# 22_USB3_0_device.net
KiCad netlist of a schematic drawn in Altium Designer
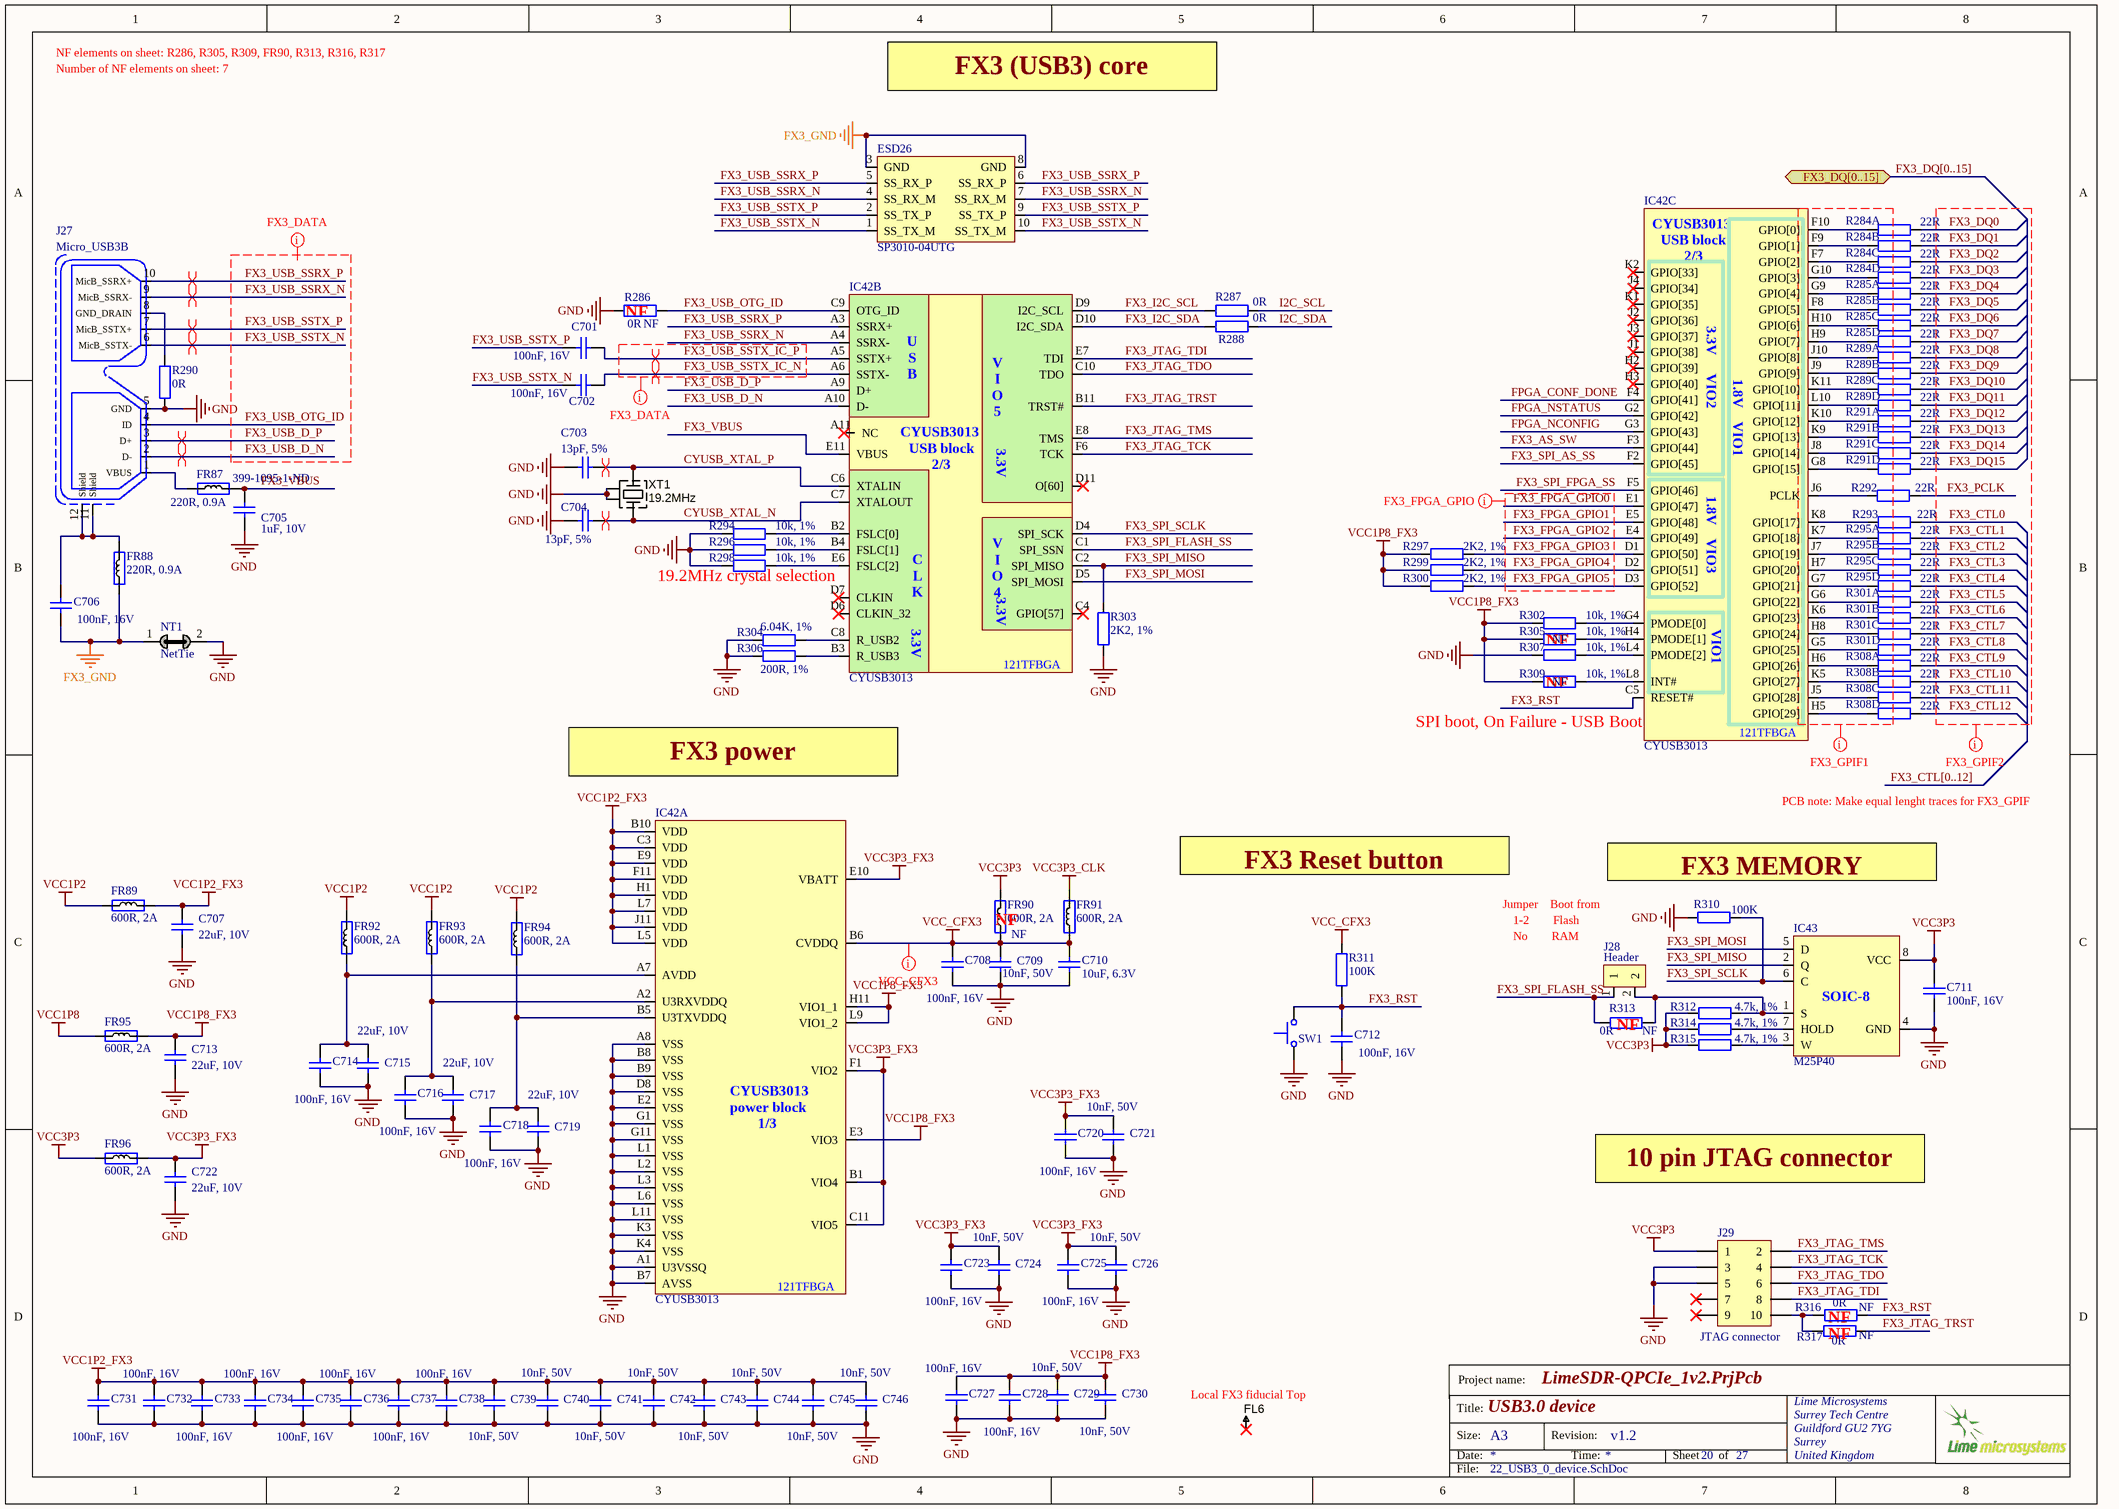
[diagram p0: 22_USB3_0_device.SchDoc]

(export (version "E")
  (design (tool "Eeschema 10.0.6"))
  (components
    (comp (ref "C701")
      (value "100nF, 16V")
      (footprint "CAP0402")
      (fields
        (field (name "TOLERANCE") "10 %")
        (field (name "MANUFACTURER") "Murata Electronics")
        (field (name "MANUFACTURER PART NUMBER") "GRM155R71C104KA88D")
      )
      (libsource (lib "LimeFPGAboard_schLib") (part "Cap_0603"))
    )
    (comp (ref "C702")
      (value "100nF, 16V")
      (footprint "CAP0402")
      (fields
        (field (name "TOLERANCE") "10 %")
        (field (name "MANUFACTURER") "Murata Electronics")
        (field (name "MANUFACTURER PART NUMBER") "GRM155R71C104KA88D")
      )
      (libsource (lib "LimeFPGAboard_schLib") (part "Cap_0603"))
    )
    (comp (ref "C703")
      (value "13pF, 5%")
      (footprint "CAP0402")
      (fields
        (field (name "TOLERANCE") "±5%")
        (field (name "MANUFACTURER") "Murata Electronics North America")
      )
      (libsource (lib "LimeFPGAboard_schLib") (part "Cap_0603"))
    )
    (comp (ref "C704")
      (value "13pF, 5%")
      (footprint "CAP0402")
      (fields
        (field (name "TOLERANCE") "±5%")
        (field (name "MANUFACTURER") "Murata Electronics North America")
      )
      (libsource (lib "LimeFPGAboard_schLib") (part "Cap_0603"))
    )
    (comp (ref "C705")
      (value "1uF, 10V")
      (footprint "CAP0603")
      (fields
        (field (name "SUPPLIER PART NUMBER 1") "399-1095-1-ND")
        (field (name "MANUFACTURER") "KEMET")
        (field (name "TOLERANCE") "±10%")
      )
      (libsource (lib "LimeFPGAboard_schLib") (part "Cap_0603"))
    )
    (comp (ref "C706")
      (value "100nF, 16V")
      (footprint "CAP0402")
      (fields
        (field (name "TOLERANCE") "10 %")
        (field (name "MANUFACTURER") "Murata Electronics")
        (field (name "MANUFACTURER PART NUMBER") "GRM155R71C104KA88D")
      )
      (libsource (lib "LimeFPGAboard_schLib") (part "Cap_0603"))
    )
    (comp (ref "C707")
      (value "22uF, 10V")
      (footprint "CAP0603")
      (fields (field (name "TOLERANCE") "20 %") (field (name "MANUFACTURER") "TDK Corporation"))
      (libsource (lib "LimeFPGAboard_schLib") (part "Cap_0603"))
    )
    (comp (ref "C708")
      (value "100nF, 16V")
      (footprint "CAP0402")
      (fields
        (field (name "TOLERANCE") "10 %")
        (field (name "MANUFACTURER") "Murata Electronics")
        (field (name "MANUFACTURER PART NUMBER") "GRM155R71C104KA88D")
      )
      (libsource (lib "LimeFPGAboard_schLib") (part "Cap_0603"))
    )
    (comp (ref "C709")
      (value "10nF, 50V")
      (footprint "CAP0402")
      (fields (field (name "TOLERANCE") "±10%") (field (name "MANUFACTURER") "Yageo"))
      (libsource (lib "LimeFPGAboard_schLib") (part "Cap_0603"))
    )
    (comp (ref "C710")
      (value "10uF, 6.3V")
      (footprint "CAP0603")
      (fields (field (name "TOLERANCE") "±20%") (field (name "MANUFACTURER") "Yageo"))
      (libsource (lib "LimeFPGAboard_schLib") (part "Cap_0603"))
    )
    (comp (ref "C711")
      (value "100nF, 16V")
      (footprint "CAP0402")
      (fields
        (field (name "TOLERANCE") "10 %")
        (field (name "MANUFACTURER") "Murata Electronics")
        (field (name "MANUFACTURER PART NUMBER") "GRM155R71C104KA88D")
      )
      (libsource (lib "LimeFPGAboard_schLib") (part "Cap_0603"))
    )
    (comp (ref "C712")
      (value "100nF, 16V")
      (footprint "CAP0402")
      (fields
        (field (name "TOLERANCE") "10 %")
        (field (name "MANUFACTURER") "Murata Electronics")
        (field (name "MANUFACTURER PART NUMBER") "GRM155R71C104KA88D")
      )
      (libsource (lib "LimeFPGAboard_schLib") (part "Cap_0603"))
    )
    (comp (ref "C713")
      (value "22uF, 10V")
      (footprint "CAP0603")
      (fields (field (name "TOLERANCE") "20 %") (field (name "MANUFACTURER") "TDK Corporation"))
      (libsource (lib "LimeFPGAboard_schLib") (part "Cap_0603"))
    )
    (comp (ref "C714")
      (value "100nF, 16V")
      (footprint "CAP0402")
      (fields
        (field (name "TOLERANCE") "10 %")
        (field (name "MANUFACTURER") "Murata Electronics")
        (field (name "MANUFACTURER PART NUMBER") "GRM155R71C104KA88D")
      )
      (libsource (lib "LimeFPGAboard_schLib") (part "Cap_0603"))
    )
    (comp (ref "C715")
      (value "22uF, 10V")
      (footprint "CAP0603")
      (fields (field (name "TOLERANCE") "20 %") (field (name "MANUFACTURER") "TDK Corporation"))
      (libsource (lib "LimeFPGAboard_schLib") (part "Cap_0603"))
    )
    (comp (ref "C716")
      (value "100nF, 16V")
      (footprint "CAP0402")
      (fields
        (field (name "TOLERANCE") "10 %")
        (field (name "MANUFACTURER") "Murata Electronics")
        (field (name "MANUFACTURER PART NUMBER") "GRM155R71C104KA88D")
      )
      (libsource (lib "LimeFPGAboard_schLib") (part "Cap_0603"))
    )
    (comp (ref "C717")
      (value "22uF, 10V")
      (footprint "CAP0603")
      (fields (field (name "TOLERANCE") "20 %") (field (name "MANUFACTURER") "TDK Corporation"))
      (libsource (lib "LimeFPGAboard_schLib") (part "Cap_0603"))
    )
    (comp (ref "C718")
      (value "100nF, 16V")
      (footprint "CAP0402")
      (fields
        (field (name "TOLERANCE") "10 %")
        (field (name "MANUFACTURER") "Murata Electronics")
        (field (name "MANUFACTURER PART NUMBER") "GRM155R71C104KA88D")
      )
      (libsource (lib "LimeFPGAboard_schLib") (part "Cap_0603"))
    )
    (comp (ref "C719")
      (value "22uF, 10V")
      (footprint "CAP0603")
      (fields (field (name "TOLERANCE") "20 %") (field (name "MANUFACTURER") "TDK Corporation"))
      (libsource (lib "LimeFPGAboard_schLib") (part "Cap_0603"))
    )
    (comp (ref "C720")
      (value "100nF, 16V")
      (footprint "CAP0402")
      (fields
        (field (name "TOLERANCE") "10 %")
        (field (name "MANUFACTURER") "Murata Electronics")
        (field (name "MANUFACTURER PART NUMBER") "GRM155R71C104KA88D")
      )
      (libsource (lib "LimeFPGAboard_schLib") (part "Cap_0603"))
    )
    (comp (ref "C721")
      (value "10nF, 50V")
      (footprint "CAP0402")
      (fields (field (name "TOLERANCE") "±10%") (field (name "MANUFACTURER") "Yageo"))
      (libsource (lib "LimeFPGAboard_schLib") (part "Cap_0603"))
    )
    (comp (ref "C722")
      (value "22uF, 10V")
      (footprint "CAP0603")
      (fields (field (name "TOLERANCE") "20 %") (field (name "MANUFACTURER") "TDK Corporation"))
      (libsource (lib "LimeFPGAboard_schLib") (part "Cap_0603"))
    )
    (comp (ref "C723")
      (value "100nF, 16V")
      (footprint "CAP0402")
      (fields
        (field (name "TOLERANCE") "10 %")
        (field (name "MANUFACTURER") "Murata Electronics")
        (field (name "MANUFACTURER PART NUMBER") "GRM155R71C104KA88D")
      )
      (libsource (lib "LimeFPGAboard_schLib") (part "Cap_0603"))
    )
    (comp (ref "C724")
      (value "10nF, 50V")
      (footprint "CAP0402")
      (fields (field (name "TOLERANCE") "±10%") (field (name "MANUFACTURER") "Yageo"))
      (libsource (lib "LimeFPGAboard_schLib") (part "Cap_0603"))
    )
    (comp (ref "C725")
      (value "100nF, 16V")
      (footprint "CAP0402")
      (fields
        (field (name "TOLERANCE") "10 %")
        (field (name "MANUFACTURER") "Murata Electronics")
        (field (name "MANUFACTURER PART NUMBER") "GRM155R71C104KA88D")
      )
      (libsource (lib "LimeFPGAboard_schLib") (part "Cap_0603"))
    )
    (comp (ref "C726")
      (value "10nF, 50V")
      (footprint "CAP0402")
      (fields (field (name "TOLERANCE") "±10%") (field (name "MANUFACTURER") "Yageo"))
      (libsource (lib "LimeFPGAboard_schLib") (part "Cap_0603"))
    )
    (comp (ref "C727")
      (value "100nF, 16V")
      (footprint "CAP0402")
      (fields
        (field (name "TOLERANCE") "10 %")
        (field (name "MANUFACTURER") "Murata Electronics")
        (field (name "MANUFACTURER PART NUMBER") "GRM155R71C104KA88D")
      )
      (libsource (lib "LimeFPGAboard_schLib") (part "Cap_0603"))
    )
    (comp (ref "C728")
      (value "100nF, 16V")
      (footprint "CAP0402")
      (fields
        (field (name "TOLERANCE") "10 %")
        (field (name "MANUFACTURER") "Murata Electronics")
        (field (name "MANUFACTURER PART NUMBER") "GRM155R71C104KA88D")
      )
      (libsource (lib "LimeFPGAboard_schLib") (part "Cap_0603"))
    )
    (comp (ref "C729")
      (value "10nF, 50V")
      (footprint "CAP0402")
      (fields (field (name "TOLERANCE") "±10%") (field (name "MANUFACTURER") "Yageo"))
      (libsource (lib "LimeFPGAboard_schLib") (part "Cap_0603"))
    )
    (comp (ref "C730")
      (value "10nF, 50V")
      (footprint "CAP0402")
      (fields (field (name "TOLERANCE") "±10%") (field (name "MANUFACTURER") "Yageo"))
      (libsource (lib "LimeFPGAboard_schLib") (part "Cap_0603"))
    )
    (comp (ref "C731")
      (value "100nF, 16V")
      (footprint "CAP0402")
      (fields
        (field (name "TOLERANCE") "10 %")
        (field (name "MANUFACTURER") "Murata Electronics")
        (field (name "MANUFACTURER PART NUMBER") "GRM155R71C104KA88D")
      )
      (libsource (lib "LimeFPGAboard_schLib") (part "Cap_0603"))
    )
    (comp (ref "C732")
      (value "100nF, 16V")
      (footprint "CAP0402")
      (fields
        (field (name "TOLERANCE") "10 %")
        (field (name "MANUFACTURER") "Murata Electronics")
        (field (name "MANUFACTURER PART NUMBER") "GRM155R71C104KA88D")
      )
      (libsource (lib "LimeFPGAboard_schLib") (part "Cap_0603"))
    )
    (comp (ref "C733")
      (value "100nF, 16V")
      (footprint "CAP0402")
      (fields
        (field (name "TOLERANCE") "10 %")
        (field (name "MANUFACTURER") "Murata Electronics")
        (field (name "MANUFACTURER PART NUMBER") "GRM155R71C104KA88D")
      )
      (libsource (lib "LimeFPGAboard_schLib") (part "Cap_0603"))
    )
    (comp (ref "C734")
      (value "100nF, 16V")
      (footprint "CAP0402")
      (fields
        (field (name "TOLERANCE") "10 %")
        (field (name "MANUFACTURER") "Murata Electronics")
        (field (name "MANUFACTURER PART NUMBER") "GRM155R71C104KA88D")
      )
      (libsource (lib "LimeFPGAboard_schLib") (part "Cap_0603"))
    )
    (comp (ref "C735")
      (value "100nF, 16V")
      (footprint "CAP0402")
      (fields
        (field (name "TOLERANCE") "10 %")
        (field (name "MANUFACTURER") "Murata Electronics")
        (field (name "MANUFACTURER PART NUMBER") "GRM155R71C104KA88D")
      )
      (libsource (lib "LimeFPGAboard_schLib") (part "Cap_0603"))
    )
    (comp (ref "C736")
      (value "100nF, 16V")
      (footprint "CAP0402")
      (fields
        (field (name "TOLERANCE") "10 %")
        (field (name "MANUFACTURER") "Murata Electronics")
        (field (name "MANUFACTURER PART NUMBER") "GRM155R71C104KA88D")
      )
      (libsource (lib "LimeFPGAboard_schLib") (part "Cap_0603"))
    )
    (comp (ref "C737")
      (value "100nF, 16V")
      (footprint "CAP0402")
      (fields
        (field (name "TOLERANCE") "10 %")
        (field (name "MANUFACTURER") "Murata Electronics")
        (field (name "MANUFACTURER PART NUMBER") "GRM155R71C104KA88D")
      )
      (libsource (lib "LimeFPGAboard_schLib") (part "Cap_0603"))
    )
    (comp (ref "C738")
      (value "100nF, 16V")
      (footprint "CAP0402")
      (fields
        (field (name "TOLERANCE") "10 %")
        (field (name "MANUFACTURER") "Murata Electronics")
        (field (name "MANUFACTURER PART NUMBER") "GRM155R71C104KA88D")
      )
      (libsource (lib "LimeFPGAboard_schLib") (part "Cap_0603"))
    )
    (comp (ref "C739")
      (value "10nF, 50V")
      (footprint "CAP0402")
      (fields (field (name "TOLERANCE") "±10%") (field (name "MANUFACTURER") "Yageo"))
      (libsource (lib "LimeFPGAboard_schLib") (part "Cap_0603"))
    )
    (comp (ref "C740")
      (value "10nF, 50V")
      (footprint "CAP0402")
      (fields (field (name "TOLERANCE") "±10%") (field (name "MANUFACTURER") "Yageo"))
      (libsource (lib "LimeFPGAboard_schLib") (part "Cap_0603"))
    )
    (comp (ref "C741")
      (value "10nF, 50V")
      (footprint "CAP0402")
      (fields (field (name "TOLERANCE") "±10%") (field (name "MANUFACTURER") "Yageo"))
      (libsource (lib "LimeFPGAboard_schLib") (part "Cap_0603"))
    )
    (comp (ref "C742")
      (value "10nF, 50V")
      (footprint "CAP0402")
      (fields (field (name "TOLERANCE") "±10%") (field (name "MANUFACTURER") "Yageo"))
      (libsource (lib "LimeFPGAboard_schLib") (part "Cap_0603"))
    )
    (comp (ref "C743")
      (value "10nF, 50V")
      (footprint "CAP0402")
      (fields (field (name "TOLERANCE") "±10%") (field (name "MANUFACTURER") "Yageo"))
      (libsource (lib "LimeFPGAboard_schLib") (part "Cap_0603"))
    )
    (comp (ref "C744")
      (value "10nF, 50V")
      (footprint "CAP0402")
      (fields (field (name "TOLERANCE") "±10%") (field (name "MANUFACTURER") "Yageo"))
      (libsource (lib "LimeFPGAboard_schLib") (part "Cap_0603"))
    )
    (comp (ref "C745")
      (value "10nF, 50V")
      (footprint "CAP0402")
      (fields (field (name "TOLERANCE") "±10%") (field (name "MANUFACTURER") "Yageo"))
      (libsource (lib "LimeFPGAboard_schLib") (part "Cap_0603"))
    )
    (comp (ref "C746")
      (value "10nF, 50V")
      (footprint "CAP0402")
      (fields (field (name "TOLERANCE") "±10%") (field (name "MANUFACTURER") "Yageo"))
      (libsource (lib "LimeFPGAboard_schLib") (part "Cap_0603"))
    )
    (comp (ref "ESD26")
      (value "SP3010-04UTG")
      (footprint "SP3010-04UTG")
      (fields (field (name "MANUFACTURER") "Littelfuse Inc"))
      (libsource (lib "LimeFPGAboard_schLib") (part "SP3010-04UTG"))
    )
    (comp (ref "FL6")
      (value "Fiducial")
      (footprint "Fiducial_local")
      (libsource (lib "LimeMicroAltiumLib_schLib") (part "Fiducial"))
    )
    (comp (ref "FR87")
      (value "220R, 0.9A")
      (footprint "RES0402")
      (fields (field (name "MANUFACTURER") "TDK Corporation"))
      (libsource (lib "LimeFPGAboard_schLib") (part "Ferrite"))
    )
    (comp (ref "FR88")
      (value "220R, 0.9A")
      (footprint "RES0402")
      (fields (field (name "MANUFACTURER") "TDK Corporation"))
      (libsource (lib "LimeFPGAboard_schLib") (part "Ferrite"))
    )
    (comp (ref "FR89")
      (value "600R, 2A")
      (footprint "RES0805")
      (fields (field (name "MANUFACTURER") "TDK"))
      (libsource (lib "LimeFPGAboard_schLib") (part "Ferrite"))
    )
    (comp (ref "FR90")
      (value "600R, 2A")
      (footprint "RES0805")
      (fields (field (name "MANUFACTURER") "TDK") (field (name "ASSEMBLY INFO") "NF"))
      (libsource (lib "LimeFPGAboard_schLib") (part "Ferrite"))
    )
    (comp (ref "FR91")
      (value "600R, 2A")
      (footprint "RES0805")
      (fields (field (name "MANUFACTURER") "TDK"))
      (libsource (lib "LimeFPGAboard_schLib") (part "Ferrite"))
    )
    (comp (ref "FR92")
      (value "600R, 2A")
      (footprint "RES0805")
      (fields (field (name "MANUFACTURER") "TDK"))
      (libsource (lib "LimeFPGAboard_schLib") (part "Ferrite"))
    )
    (comp (ref "FR93")
      (value "600R, 2A")
      (footprint "RES0805")
      (fields (field (name "MANUFACTURER") "TDK"))
      (libsource (lib "LimeFPGAboard_schLib") (part "Ferrite"))
    )
    (comp (ref "FR94")
      (value "600R, 2A")
      (footprint "RES0805")
      (fields (field (name "MANUFACTURER") "TDK"))
      (libsource (lib "LimeFPGAboard_schLib") (part "Ferrite"))
    )
    (comp (ref "FR95")
      (value "600R, 2A")
      (footprint "RES0805")
      (fields (field (name "MANUFACTURER") "TDK"))
      (libsource (lib "LimeFPGAboard_schLib") (part "Ferrite"))
    )
    (comp (ref "FR96")
      (value "600R, 2A")
      (footprint "RES0805")
      (fields (field (name "MANUFACTURER") "TDK"))
      (libsource (lib "LimeFPGAboard_schLib") (part "Ferrite"))
    )
    (comp (ref "IC42")
      (value "CYUSB3013")
      (footprint "CYUSB3013")
      (description "Cypress USB3.0 chip")
      (fields (field (name "MANUFACTURER") "Cypress Semiconductor Corp"))
      (libsource (lib "LimeMicroAltiumLib_schLib") (part "CYUSB3013"))
    )
    (comp (ref "IC43")
      (value "M25P40")
      (footprint "M25P40-VMN6TPB_SO8N")
      (fields (field (name "MANUFACTURER") "Micron Technology Inc"))
      (libsource (lib "LimeFPGAboard_schLib") (part "M25P40"))
    )
    (comp (ref "J27")
      (value "Micro_USB3B")
      (footprint "microUSB3B_SM_v2")
      (fields (field (name "MANUFACTURER") "Amphenol Commercial Products"))
      (libsource (lib "LimeFPGAboard_schLib") (part "Micro_USB3_B"))
    )
    (comp (ref "J28")
      (value "Header")
      (footprint "HDR_1x2")
      (fields (field (name "MANUFACTURER") "3M"))
      (libsource (lib "LimeFPGAboard_schLib") (part "Jumper"))
    )
    (comp (ref "J29")
      (value "JTAG connector")
      (footprint "SWD_10_pin")
      (description "Header, 5-Pin, Dual row")
      (fields (field (name "MANUFACTURER") "Harwin Inc"))
      (libsource (lib "LimeMicroAltiumLib_schLib") (part "Header 5X2_SWD"))
    )
    (comp (ref "NT1")
      (value "NetTie")
      (footprint "NetTie_Wide2")
      (libsource (lib "LimeFPGAboard_schLib") (part "NetTie"))
    )
    (comp (ref "R284")
      (value "22R")
      (footprint "ChipResistorArray")
      (fields (field (name "TOLERANCE") "±5%") (field (name "MANUFACTURER") "Yageo"))
      (libsource (lib "LimeFPGAboard_schLib") (part "ResArray_0802"))
    )
    (comp (ref "R285")
      (value "22R")
      (footprint "ChipResistorArray")
      (fields (field (name "TOLERANCE") "±5%") (field (name "MANUFACTURER") "Yageo"))
      (libsource (lib "LimeFPGAboard_schLib") (part "ResArray_0802"))
    )
    (comp (ref "R286")
      (value "0R")
      (footprint "RES0402")
      (fields (field (name "MANUFACTURER") "Yageo") (field (name "ASSEMBLY INFO") "NF"))
      (libsource (lib "LimeFPGAboard_schLib") (part "Res_0402"))
    )
    (comp (ref "R287")
      (value "0R")
      (footprint "RES0402")
      (fields (field (name "MANUFACTURER") "Yageo"))
      (libsource (lib "LimeFPGAboard_schLib") (part "Res_0402"))
    )
    (comp (ref "R288")
      (value "0R")
      (footprint "RES0402")
      (fields (field (name "MANUFACTURER") "Yageo"))
      (libsource (lib "LimeFPGAboard_schLib") (part "Res_0402"))
    )
    (comp (ref "R289")
      (value "22R")
      (footprint "ChipResistorArray")
      (fields (field (name "TOLERANCE") "±5%") (field (name "MANUFACTURER") "Yageo"))
      (libsource (lib "LimeFPGAboard_schLib") (part "ResArray_0802"))
    )
    (comp (ref "R290")
      (value "0R")
      (footprint "RES0402")
      (fields (field (name "MANUFACTURER") "Yageo"))
      (libsource (lib "LimeFPGAboard_schLib") (part "Res_0402"))
    )
    (comp (ref "R291")
      (value "22R")
      (footprint "ChipResistorArray")
      (fields (field (name "TOLERANCE") "±5%") (field (name "MANUFACTURER") "Yageo"))
      (libsource (lib "LimeFPGAboard_schLib") (part "ResArray_0802"))
    )
    (comp (ref "R292")
      (value "22R")
      (footprint "RES0402")
      (fields (field (name "TOLERANCE") "±1%") (field (name "MANUFACTURER") "Yageo"))
      (libsource (lib "LimeFPGAboard_schLib") (part "Res_0402"))
    )
    (comp (ref "R293")
      (value "22R")
      (footprint "RES0402")
      (fields (field (name "TOLERANCE") "±1%") (field (name "MANUFACTURER") "Yageo"))
      (libsource (lib "LimeFPGAboard_schLib") (part "Res_0402"))
    )
    (comp (ref "R294")
      (value "10k, 1%")
      (footprint "RES0402")
      (fields (field (name "MANUFACTURER") "Yageo") (field (name "TOLERANCE") "±1%"))
      (libsource (lib "LimeMicroAltiumLib_schLib") (part "Res_0402"))
    )
    (comp (ref "R295")
      (value "22R")
      (footprint "ChipResistorArray")
      (fields (field (name "TOLERANCE") "±5%") (field (name "MANUFACTURER") "Yageo"))
      (libsource (lib "LimeFPGAboard_schLib") (part "ResArray_0802"))
    )
    (comp (ref "R296")
      (value "10k, 1%")
      (footprint "RES0402")
      (fields (field (name "MANUFACTURER") "Yageo") (field (name "TOLERANCE") "±1%"))
      (libsource (lib "LimeMicroAltiumLib_schLib") (part "Res_0402"))
    )
    (comp (ref "R297")
      (value "2K2, 1%")
      (footprint "RES0402")
      (fields (field (name "TOLERANCE") "±1%"))
      (libsource (lib "LimeFPGAboard_schLib") (part "Res_0402"))
    )
    (comp (ref "R298")
      (value "10k, 1%")
      (footprint "RES0402")
      (fields (field (name "MANUFACTURER") "Yageo") (field (name "TOLERANCE") "±1%"))
      (libsource (lib "LimeMicroAltiumLib_schLib") (part "Res_0402"))
    )
    (comp (ref "R299")
      (value "2K2, 1%")
      (footprint "RES0402")
      (fields (field (name "TOLERANCE") "±1%"))
      (libsource (lib "LimeFPGAboard_schLib") (part "Res_0402"))
    )
    (comp (ref "R300")
      (value "2K2, 1%")
      (footprint "RES0402")
      (fields (field (name "TOLERANCE") "±1%"))
      (libsource (lib "LimeFPGAboard_schLib") (part "Res_0402"))
    )
    (comp (ref "R301")
      (value "22R")
      (footprint "ChipResistorArray")
      (fields (field (name "TOLERANCE") "±5%") (field (name "MANUFACTURER") "Yageo"))
      (libsource (lib "LimeFPGAboard_schLib") (part "ResArray_0802"))
    )
    (comp (ref "R302")
      (value "10k, 1%")
      (footprint "RES0402")
      (fields (field (name "MANUFACTURER") "Yageo") (field (name "TOLERANCE") "±1%"))
      (libsource (lib "LimeMicroAltiumLib_schLib") (part "Res_0402"))
    )
    (comp (ref "R303")
      (value "2K2, 1%")
      (footprint "RES0402")
      (fields (field (name "TOLERANCE") "±1%"))
      (libsource (lib "LimeFPGAboard_schLib") (part "Res_0402"))
    )
    (comp (ref "R304")
      (value "6.04K, 1%")
      (footprint "RES0402")
      (fields (field (name "MANUFACTURER") "Rohm Semiconductor") (field (name "TOLERANCE") "±1%"))
      (libsource (lib "LimeFPGAboard_schLib") (part "Res_0402"))
    )
    (comp (ref "R305")
      (value "10k, 1%")
      (footprint "RES0402")
      (fields
        (field (name "ASSEMBLY INFO") "NF")
        (field (name "MANUFACTURER") "Yageo")
        (field (name "TOLERANCE") "±1%")
      )
      (libsource (lib "LimeMicroAltiumLib_schLib") (part "Res_0402"))
    )
    (comp (ref "R306")
      (value "200R, 1%")
      (footprint "RES0402")
      (fields (field (name "MANUFACTURER") "Stackpole Electronics Inc") (field (name "TOLERANCE") "±1%"))
      (libsource (lib "LimeFPGAboard_schLib") (part "Res_0402"))
    )
    (comp (ref "R307")
      (value "10k, 1%")
      (footprint "RES0402")
      (fields (field (name "MANUFACTURER") "Yageo") (field (name "TOLERANCE") "±1%"))
      (libsource (lib "LimeMicroAltiumLib_schLib") (part "Res_0402"))
    )
    (comp (ref "R308")
      (value "22R")
      (footprint "ChipResistorArray")
      (fields (field (name "TOLERANCE") "±5%") (field (name "MANUFACTURER") "Yageo"))
      (libsource (lib "LimeFPGAboard_schLib") (part "ResArray_0802"))
    )
    (comp (ref "R309")
      (value "10k, 1%")
      (footprint "RES0402")
      (fields
        (field (name "ASSEMBLY INFO") "NF")
        (field (name "MANUFACTURER") "Yageo")
        (field (name "TOLERANCE") "±1%")
      )
      (libsource (lib "LimeMicroAltiumLib_schLib") (part "Res_0402"))
    )
    (comp (ref "R310")
      (value "100K")
      (footprint "RES0402")
      (fields
        (field (name "TOLERANCE") "±5%")
        (field (name "MANUFACTURER") "Panasonic Electronic Components")
      )
      (libsource (lib "LimeFPGAboard_schLib") (part "Res_0402"))
    )
    (comp (ref "R311")
      (value "100K")
      (footprint "RES0402")
      (fields
        (field (name "TOLERANCE") "±5%")
        (field (name "MANUFACTURER") "Panasonic Electronic Components")
      )
      (libsource (lib "LimeFPGAboard_schLib") (part "Res_0402"))
    )
    (comp (ref "R312")
      (value "4.7k, 1%")
      (footprint "RES0402")
      (fields (field (name "MANUFACTURER") "Yageo") (field (name "TOLERANCE") "±1%"))
      (libsource (lib "LimeMicroAltiumLib_schLib") (part "Res_0402"))
    )
    (comp (ref "R313")
      (value "0R")
      (footprint "RES0402")
      (fields
        (field (name "ASSEMBLY INFO") "NF")
        (field (name "MANUFACTURER") "Yageo")
        (field (name "TOLERANCE") "Jumper")
      )
      (libsource (lib "LimeMicroAltiumLib_schLib") (part "Res_0402"))
    )
    (comp (ref "R314")
      (value "4.7k, 1%")
      (footprint "RES0402")
      (fields (field (name "MANUFACTURER") "Yageo") (field (name "TOLERANCE") "±1%"))
      (libsource (lib "LimeMicroAltiumLib_schLib") (part "Res_0402"))
    )
    (comp (ref "R315")
      (value "4.7k, 1%")
      (footprint "RES0402")
      (fields (field (name "MANUFACTURER") "Yageo") (field (name "TOLERANCE") "±1%"))
      (libsource (lib "LimeMicroAltiumLib_schLib") (part "Res_0402"))
    )
    (comp (ref "R316")
      (value "0R")
      (footprint "RES0402")
      (fields
        (field (name "ASSEMBLY INFO") "NF")
        (field (name "MANUFACTURER") "Yageo")
        (field (name "TOLERANCE") "Jumper")
      )
      (libsource (lib "LimeMicroAltiumLib_schLib") (part "Res_0402"))
    )
    (comp (ref "R317")
      (value "0R")
      (footprint "RES0402")
      (fields
        (field (name "ASSEMBLY INFO") "NF")
        (field (name "MANUFACTURER") "Yageo")
        (field (name "TOLERANCE") "Jumper")
      )
      (libsource (lib "LimeMicroAltiumLib_schLib") (part "Res_0402"))
    )
    (comp (ref "SW1")
      (value "Switch, tactile")
      (footprint "SW_tactile")
      (fields (field (name "MANUFACTURER") "Omron Electronics Inc-EMC Div"))
      (libsource (lib "LimeFPGAboard_schLib") (part "Button"))
    )
    (comp (ref "XT1")
      (value "19.2MHz")
      (footprint "CRYSTAL_4-LCC_v2")
      (description "Oscillator Crystal 19.2 MHz")
      (fields (field (name "MANUFACTURER") "CTS-Frequency Controls"))
      (libsource (lib "LimeFPGAboard_schLib") (part "CRYSTAL_19M2"))
    )
  )
  (nets
    (net (code "1") (name "/CYUSB_XTAL_N") (class "Default")
      (node (ref "C704") (pin "2") (pinfunction "2_2") (pintype "passive"))
      (node (ref "IC42") (pin "C7") (pinfunction "XTALOUT_C7") (pintype "passive"))
      (node (ref "XT1") (pin "3") (pinfunction "X_3") (pintype "passive"))
    )
    (net (code "2") (name "/CYUSB_XTAL_P") (class "Default")
      (node (ref "C703") (pin "2") (pinfunction "2_2") (pintype "passive"))
      (node (ref "IC42") (pin "C6") (pinfunction "XTALIN_C6") (pintype "passive"))
      (node (ref "XT1") (pin "1") (pinfunction "X_1") (pintype "passive"))
    )
    (net (code "3") (name "/FPGA_CONF_DONE") (class "Default")
      (node (ref "IC42") (pin "F4") (pinfunction "GPIO[41]_F4") (pintype "passive"))
    )
    (net (code "4") (name "/FPGA_NCONFIG") (class "Default")
      (node (ref "IC42") (pin "G3") (pinfunction "GPIO[43]_G3") (pintype "passive"))
    )
    (net (code "5") (name "/FPGA_NSTATUS") (class "Default")
      (node (ref "IC42") (pin "G2") (pinfunction "GPIO[42]_G2") (pintype "passive"))
    )
    (net (code "6") (name "/FX3_AS_SW") (class "Default")
      (node (ref "IC42") (pin "F3") (pinfunction "GPIO[44]_F3") (pintype "passive"))
    )
    (net (code "7") (name "/FX3_CTL0") (class "Default")
      (node (ref "R293") (pin "2") (pinfunction "2_2") (pintype "passive"))
    )
    (net (code "8") (name "/FX3_CTL1") (class "Default")
      (node (ref "R295") (pin "2") (pinfunction "2_2") (pintype "passive"))
    )
    (net (code "9") (name "/FX3_CTL2") (class "Default")
      (node (ref "R295") (pin "4") (pinfunction "4_4") (pintype "passive"))
    )
    (net (code "10") (name "/FX3_CTL3") (class "Default")
      (node (ref "R295") (pin "6") (pinfunction "6_6") (pintype "passive"))
    )
    (net (code "11") (name "/FX3_CTL4") (class "Default")
      (node (ref "R295") (pin "8") (pinfunction "8_8") (pintype "passive"))
    )
    (net (code "12") (name "/FX3_CTL5") (class "Default")
      (node (ref "R301") (pin "2") (pinfunction "2_2") (pintype "passive"))
    )
    (net (code "13") (name "/FX3_CTL6") (class "Default")
      (node (ref "R301") (pin "4") (pinfunction "4_4") (pintype "passive"))
    )
    (net (code "14") (name "/FX3_CTL7") (class "Default")
      (node (ref "R301") (pin "6") (pinfunction "6_6") (pintype "passive"))
    )
    (net (code "15") (name "/FX3_CTL8") (class "Default")
      (node (ref "R301") (pin "8") (pinfunction "8_8") (pintype "passive"))
    )
    (net (code "16") (name "/FX3_CTL9") (class "Default")
      (node (ref "R308") (pin "2") (pinfunction "2_2") (pintype "passive"))
    )
    (net (code "17") (name "/FX3_CTL10") (class "Default")
      (node (ref "R308") (pin "4") (pinfunction "4_4") (pintype "passive"))
    )
    (net (code "18") (name "/FX3_CTL11") (class "Default")
      (node (ref "R308") (pin "6") (pinfunction "6_6") (pintype "passive"))
    )
    (net (code "19") (name "/FX3_CTL12") (class "Default")
      (node (ref "R308") (pin "8") (pinfunction "8_8") (pintype "passive"))
    )
    (net (code "21") (name "/FX3_DQ0") (class "Default")
      (node (ref "R284") (pin "2") (pinfunction "2_2") (pintype "passive"))
    )
    (net (code "22") (name "/FX3_DQ1") (class "Default")
      (node (ref "R284") (pin "4") (pinfunction "4_4") (pintype "passive"))
    )
    (net (code "23") (name "/FX3_DQ2") (class "Default")
      (node (ref "R284") (pin "6") (pinfunction "6_6") (pintype "passive"))
    )
    (net (code "24") (name "/FX3_DQ3") (class "Default")
      (node (ref "R284") (pin "8") (pinfunction "8_8") (pintype "passive"))
    )
    (net (code "25") (name "/FX3_DQ4") (class "Default")
      (node (ref "R285") (pin "2") (pinfunction "2_2") (pintype "passive"))
    )
    (net (code "26") (name "/FX3_DQ5") (class "Default")
      (node (ref "R285") (pin "4") (pinfunction "4_4") (pintype "passive"))
    )
    (net (code "27") (name "/FX3_DQ6") (class "Default")
      (node (ref "R285") (pin "6") (pinfunction "6_6") (pintype "passive"))
    )
    (net (code "28") (name "/FX3_DQ7") (class "Default")
      (node (ref "R285") (pin "8") (pinfunction "8_8") (pintype "passive"))
    )
    (net (code "29") (name "/FX3_DQ8") (class "Default")
      (node (ref "R289") (pin "2") (pinfunction "2_2") (pintype "passive"))
    )
    (net (code "30") (name "/FX3_DQ9") (class "Default")
      (node (ref "R289") (pin "4") (pinfunction "4_4") (pintype "passive"))
    )
    (net (code "31") (name "/FX3_DQ10") (class "Default")
      (node (ref "R289") (pin "6") (pinfunction "6_6") (pintype "passive"))
    )
    (net (code "32") (name "/FX3_DQ11") (class "Default")
      (node (ref "R289") (pin "8") (pinfunction "8_8") (pintype "passive"))
    )
    (net (code "33") (name "/FX3_DQ12") (class "Default")
      (node (ref "R291") (pin "2") (pinfunction "2_2") (pintype "passive"))
    )
    (net (code "34") (name "/FX3_DQ13") (class "Default")
      (node (ref "R291") (pin "4") (pinfunction "4_4") (pintype "passive"))
    )
    (net (code "35") (name "/FX3_DQ14") (class "Default")
      (node (ref "R291") (pin "6") (pinfunction "6_6") (pintype "passive"))
    )
    (net (code "36") (name "/FX3_DQ15") (class "Default")
      (node (ref "R291") (pin "8") (pinfunction "8_8") (pintype "passive"))
    )
    (net (code "38") (name "/FX3_FPGA_GPIO0") (class "Default")
      (node (ref "IC42") (pin "E1") (pinfunction "GPIO[47]_E1") (pintype "passive"))
    )
    (net (code "39") (name "/FX3_FPGA_GPIO1") (class "Default")
      (node (ref "IC42") (pin "E5") (pinfunction "GPIO[48]_E5") (pintype "passive"))
    )
    (net (code "40") (name "/FX3_FPGA_GPIO2") (class "Default")
      (node (ref "IC42") (pin "E4") (pinfunction "GPIO[49]_E4") (pintype "passive"))
    )
    (net (code "41") (name "/FX3_FPGA_GPIO3") (class "Default")
      (node (ref "IC42") (pin "D1") (pinfunction "GPIO[50]_D1") (pintype "passive"))
      (node (ref "R297") (pin "2") (pinfunction "2_2") (pintype "passive"))
    )
    (net (code "42") (name "/FX3_FPGA_GPIO4") (class "Default")
      (node (ref "IC42") (pin "D2") (pinfunction "GPIO[51]_D2") (pintype "passive"))
      (node (ref "R299") (pin "2") (pinfunction "2_2") (pintype "passive"))
    )
    (net (code "43") (name "/FX3_FPGA_GPIO5") (class "Default")
      (node (ref "IC42") (pin "D3") (pinfunction "GPIO[52]_D3") (pintype "passive"))
      (node (ref "R300") (pin "2") (pinfunction "2_2") (pintype "passive"))
    )
    (net (code "44") (name "/FX3_I2C_SCL") (class "Default")
      (node (ref "IC42") (pin "D9") (pinfunction "I2C_SCL_D9") (pintype "passive"))
      (node (ref "R287") (pin "2") (pinfunction "2_2") (pintype "passive"))
    )
    (net (code "45") (name "/FX3_I2C_SDA") (class "Default")
      (node (ref "IC42") (pin "D10") (pinfunction "I2C_SDA_D10") (pintype "passive"))
      (node (ref "R288") (pin "2") (pinfunction "2_2") (pintype "passive"))
    )
    (net (code "46") (name "/FX3_JTAG_TCK") (class "Default")
      (node (ref "IC42") (pin "F6") (pinfunction "TCK_F6") (pintype "passive"))
      (node (ref "J29") (pin "4") (pinfunction "4_4") (pintype "passive"))
    )
    (net (code "47") (name "/FX3_JTAG_TDI") (class "Default")
      (node (ref "IC42") (pin "E7") (pinfunction "TDI_E7") (pintype "passive"))
      (node (ref "J29") (pin "8") (pinfunction "8_8") (pintype "passive"))
    )
    (net (code "48") (name "/FX3_JTAG_TDO") (class "Default")
      (node (ref "IC42") (pin "C10") (pinfunction "TDO_C10") (pintype "passive"))
      (node (ref "J29") (pin "6") (pinfunction "6_6") (pintype "passive"))
    )
    (net (code "49") (name "/FX3_JTAG_TMS") (class "Default")
      (node (ref "IC42") (pin "E8") (pinfunction "TMS_E8") (pintype "passive"))
      (node (ref "J29") (pin "2") (pinfunction "2_2") (pintype "passive"))
    )
    (net (code "50") (name "/FX3_JTAG_TRST") (class "Default")
      (node (ref "IC42") (pin "B11") (pinfunction "TRST#_B11") (pintype "passive"))
      (node (ref "R317") (pin "1") (pinfunction "1_1") (pintype "passive"))
    )
    (net (code "51") (name "/FX3_PCLK") (class "Default")
      (node (ref "R292") (pin "2") (pinfunction "2_2") (pintype "passive"))
    )
    (net (code "52") (name "/FX3_RST") (class "Default")
      (node (ref "C712") (pin "1") (pinfunction "1_1") (pintype "passive"))
      (node (ref "IC42") (pin "C5") (pinfunction "RESET#_C5") (pintype "passive"))
      (node (ref "R311") (pin "2") (pinfunction "2_2") (pintype "passive"))
      (node (ref "R316") (pin "1") (pinfunction "1_1") (pintype "passive"))
      (node (ref "SW1") (pin "2") (pinfunction "2_2") (pintype "passive"))
    )
    (net (code "53") (name "/FX3_SPI_AS_SS") (class "Default")
      (node (ref "IC42") (pin "F2") (pinfunction "GPIO[45]_F2") (pintype "passive"))
    )
    (net (code "54") (name "/FX3_SPI_FLASH_SS") (class "Default")
      (node (ref "IC42") (pin "C1") (pinfunction "SPI_SSN_C1") (pintype "passive"))
      (node (ref "J28") (pin "1") (pinfunction "1_1") (pintype "passive"))
      (node (ref "R313") (pin "1") (pinfunction "1_1") (pintype "passive"))
    )
    (net (code "55") (name "/FX3_SPI_FPGA_SS") (class "Default")
      (node (ref "IC42") (pin "F5") (pinfunction "GPIO[46]_F5") (pintype "passive"))
    )
    (net (code "56") (name "/FX3_SPI_MISO") (class "Default")
      (node (ref "IC42") (pin "C2") (pinfunction "SPI_MISO_C2") (pintype "passive"))
      (node (ref "IC43") (pin "2") (pinfunction "Q_2") (pintype "passive"))
      (node (ref "R303") (pin "1") (pinfunction "1_1") (pintype "passive"))
    )
    (net (code "57") (name "/FX3_SPI_MOSI") (class "Default")
      (node (ref "IC42") (pin "D5") (pinfunction "SPI_MOSI_D5") (pintype "passive"))
      (node (ref "IC43") (pin "5") (pinfunction "D_5") (pintype "passive"))
    )
    (net (code "58") (name "/FX3_SPI_SCLK") (class "Default")
      (node (ref "IC42") (pin "D4") (pinfunction "SPI_SCK_D4") (pintype "passive"))
      (node (ref "IC43") (pin "6") (pinfunction "C_6") (pintype "passive"))
      (node (ref "R310") (pin "2") (pinfunction "2_2") (pintype "passive"))
    )
    (net (code "59") (name "/FX3_USB_D_N") (class "Default")
      (node (ref "IC42") (pin "A10") (pinfunction "D-_A10") (pintype "passive"))
      (node (ref "J27") (pin "2") (pinfunction "D-_2") (pintype "passive"))
    )
    (net (code "60") (name "/FX3_USB_D_P") (class "Default")
      (node (ref "IC42") (pin "A9") (pinfunction "D+_A9") (pintype "passive"))
      (node (ref "J27") (pin "3") (pinfunction "D+_3") (pintype "passive"))
    )
    (net (code "61") (name "/FX3_USB_OTG_ID") (class "Default")
      (node (ref "IC42") (pin "C9") (pinfunction "OTG_ID_C9") (pintype "passive"))
      (node (ref "J27") (pin "4") (pinfunction "ID_4") (pintype "passive"))
      (node (ref "R286") (pin "2") (pinfunction "2_2") (pintype "passive"))
    )
    (net (code "62") (name "/FX3_USB_SSRX_N") (class "Default")
      (node (ref "ESD26") (pin "4") (pinfunction "SS_RX_M_4") (pintype "passive"))
      (node (ref "ESD26") (pin "7") (pinfunction "SS_RX_M_7") (pintype "passive"))
      (node (ref "IC42") (pin "A4") (pinfunction "SSRX-_A4") (pintype "passive"))
      (node (ref "J27") (pin "9") (pinfunction "MicB_SSRX-_9") (pintype "passive"))
    )
    (net (code "63") (name "/FX3_USB_SSRX_P") (class "Default")
      (node (ref "ESD26") (pin "5") (pinfunction "SS_RX_P_5") (pintype "passive"))
      (node (ref "ESD26") (pin "6") (pinfunction "SS_RX_P_6") (pintype "passive"))
      (node (ref "IC42") (pin "A3") (pinfunction "SSRX+_A3") (pintype "passive"))
      (node (ref "J27") (pin "10") (pinfunction "MicB_SSRX+_10") (pintype "passive"))
    )
    (net (code "64") (name "/FX3_USB_SSTX_IC_N") (class "Default")
      (node (ref "C702") (pin "2") (pinfunction "2_2") (pintype "passive"))
      (node (ref "IC42") (pin "A6") (pinfunction "SSTX-_A6") (pintype "passive"))
    )
    (net (code "65") (name "/FX3_USB_SSTX_IC_P") (class "Default")
      (node (ref "C701") (pin "1") (pinfunction "1_1") (pintype "passive"))
      (node (ref "IC42") (pin "A5") (pinfunction "SSTX+_A5") (pintype "passive"))
    )
    (net (code "66") (name "/FX3_USB_SSTX_N") (class "Default")
      (node (ref "C702") (pin "1") (pinfunction "1_1") (pintype "passive"))
      (node (ref "ESD26") (pin "1") (pinfunction "SS_TX_M_1") (pintype "passive"))
      (node (ref "ESD26") (pin "10") (pinfunction "SS_TX_M_10") (pintype "passive"))
      (node (ref "J27") (pin "6") (pinfunction "MicB_SSTX-_6") (pintype "passive"))
    )
    (net (code "67") (name "/FX3_USB_SSTX_P") (class "Default")
      (node (ref "C701") (pin "2") (pinfunction "2_2") (pintype "passive"))
      (node (ref "ESD26") (pin "2") (pinfunction "SS_TX_P_2") (pintype "passive"))
      (node (ref "ESD26") (pin "9") (pinfunction "SS_TX_P_9") (pintype "passive"))
      (node (ref "J27") (pin "7") (pinfunction "MicB_SSTX+_7") (pintype "passive"))
    )
    (net (code "68") (name "/FX3_VBUS") (class "Default")
      (node (ref "C705") (pin "2") (pinfunction "2_2") (pintype "passive"))
      (node (ref "FR87") (pin "2") (pinfunction "2_2") (pintype "passive"))
      (node (ref "IC42") (pin "E11") (pinfunction "VBUS_E11") (pintype "power_in"))
    )
    (net (code "69") (name "/I2C_SCL") (class "Default")
      (node (ref "R287") (pin "1") (pinfunction "1_1") (pintype "passive"))
    )
    (net (code "70") (name "/I2C_SDA") (class "Default")
      (node (ref "R288") (pin "1") (pinfunction "1_1") (pintype "passive"))
    )
    (net (code "71") (name "FX3_GND") (class "Default")
      (node (ref "C706") (pin "2") (pinfunction "2_2") (pintype "passive"))
      (node (ref "ESD26") (pin "3") (pinfunction "GND_3") (pintype "passive"))
      (node (ref "ESD26") (pin "8") (pinfunction "GND_8") (pintype "passive"))
      (node (ref "FR88") (pin "1") (pinfunction "1_1") (pintype "passive"))
      (node (ref "NT1") (pin "1") (pinfunction "1_1") (pintype "passive"))
    )
    (net (code "72") (name "GND") (class "Default")
      (node (ref "C703") (pin "1") (pinfunction "1_1") (pintype "passive"))
      (node (ref "C704") (pin "1") (pinfunction "1_1") (pintype "passive"))
      (node (ref "C705") (pin "1") (pinfunction "1_1") (pintype "passive"))
      (node (ref "C707") (pin "1") (pinfunction "1_1") (pintype "passive"))
      (node (ref "C708") (pin "2") (pinfunction "2_2") (pintype "passive"))
      (node (ref "C709") (pin "1") (pinfunction "1_1") (pintype "passive"))
      (node (ref "C710") (pin "1") (pinfunction "1_1") (pintype "passive"))
      (node (ref "C711") (pin "2") (pinfunction "2_2") (pintype "passive"))
      (node (ref "C712") (pin "2") (pinfunction "2_2") (pintype "passive"))
      (node (ref "C713") (pin "1") (pinfunction "1_1") (pintype "passive"))
      (node (ref "C714") (pin "2") (pinfunction "2_2") (pintype "passive"))
      (node (ref "C715") (pin "1") (pinfunction "1_1") (pintype "passive"))
      (node (ref "C716") (pin "2") (pinfunction "2_2") (pintype "passive"))
      (node (ref "C717") (pin "1") (pinfunction "1_1") (pintype "passive"))
      (node (ref "C718") (pin "2") (pinfunction "2_2") (pintype "passive"))
      (node (ref "C719") (pin "1") (pinfunction "1_1") (pintype "passive"))
      (node (ref "C720") (pin "2") (pinfunction "2_2") (pintype "passive"))
      (node (ref "C721") (pin "1") (pinfunction "1_1") (pintype "passive"))
      (node (ref "C722") (pin "1") (pinfunction "1_1") (pintype "passive"))
      (node (ref "C723") (pin "2") (pinfunction "2_2") (pintype "passive"))
      (node (ref "C724") (pin "1") (pinfunction "1_1") (pintype "passive"))
      (node (ref "C725") (pin "2") (pinfunction "2_2") (pintype "passive"))
      (node (ref "C726") (pin "1") (pinfunction "1_1") (pintype "passive"))
      (node (ref "C727") (pin "2") (pinfunction "2_2") (pintype "passive"))
      (node (ref "C728") (pin "2") (pinfunction "2_2") (pintype "passive"))
      (node (ref "C729") (pin "1") (pinfunction "1_1") (pintype "passive"))
      (node (ref "C730") (pin "1") (pinfunction "1_1") (pintype "passive"))
      (node (ref "C731") (pin "2") (pinfunction "2_2") (pintype "passive"))
      (node (ref "C732") (pin "2") (pinfunction "2_2") (pintype "passive"))
      (node (ref "C733") (pin "2") (pinfunction "2_2") (pintype "passive"))
      (node (ref "C734") (pin "2") (pinfunction "2_2") (pintype "passive"))
      (node (ref "C735") (pin "2") (pinfunction "2_2") (pintype "passive"))
      (node (ref "C736") (pin "2") (pinfunction "2_2") (pintype "passive"))
      (node (ref "C737") (pin "2") (pinfunction "2_2") (pintype "passive"))
      (node (ref "C738") (pin "2") (pinfunction "2_2") (pintype "passive"))
      (node (ref "C739") (pin "1") (pinfunction "1_1") (pintype "passive"))
      (node (ref "C740") (pin "1") (pinfunction "1_1") (pintype "passive"))
      (node (ref "C741") (pin "1") (pinfunction "1_1") (pintype "passive"))
      (node (ref "C742") (pin "1") (pinfunction "1_1") (pintype "passive"))
      (node (ref "C743") (pin "1") (pinfunction "1_1") (pintype "passive"))
      (node (ref "C744") (pin "1") (pinfunction "1_1") (pintype "passive"))
      (node (ref "C745") (pin "1") (pinfunction "1_1") (pintype "passive"))
      (node (ref "C746") (pin "1") (pinfunction "1_1") (pintype "passive"))
      (node (ref "IC42") (pin "A1") (pinfunction "U3VSSQ_A1") (pintype "power_in"))
      (node (ref "IC42") (pin "A8") (pinfunction "VSS_A8") (pintype "power_in"))
      (node (ref "IC42") (pin "B7") (pinfunction "AVSS_B7") (pintype "power_in"))
      (node (ref "IC42") (pin "B8") (pinfunction "VSS_B8") (pintype "power_in"))
      (node (ref "IC42") (pin "B9") (pinfunction "VSS_B9") (pintype "power_in"))
      (node (ref "IC42") (pin "D8") (pinfunction "VSS_D8") (pintype "power_in"))
      (node (ref "IC42") (pin "E2") (pinfunction "VSS_E2") (pintype "power_in"))
      (node (ref "IC42") (pin "G1") (pinfunction "VSS_G1") (pintype "power_in"))
      (node (ref "IC42") (pin "G11") (pinfunction "VSS_G11") (pintype "power_in"))
      (node (ref "IC42") (pin "K3") (pinfunction "VSS_K3") (pintype "power_in"))
      (node (ref "IC42") (pin "K4") (pinfunction "VSS_K4") (pintype "power_in"))
      (node (ref "IC42") (pin "L1") (pinfunction "VSS_L1") (pintype "power_in"))
      (node (ref "IC42") (pin "L11") (pinfunction "VSS_L11") (pintype "power_in"))
      (node (ref "IC42") (pin "L2") (pinfunction "VSS_L2") (pintype "power_in"))
      (node (ref "IC42") (pin "L3") (pinfunction "VSS_L3") (pintype "power_in"))
      (node (ref "IC42") (pin "L6") (pinfunction "VSS_L6") (pintype "power_in"))
      (node (ref "IC43") (pin "4") (pinfunction "GND_4") (pintype "passive"))
      (node (ref "J27") (pin "5") (pinfunction "GND_5") (pintype "passive"))
      (node (ref "J29") (pin "3") (pinfunction "3_3") (pintype "passive"))
      (node (ref "J29") (pin "5") (pinfunction "5_5") (pintype "passive"))
      (node (ref "NT1") (pin "2") (pinfunction "2_2") (pintype "passive"))
      (node (ref "R286") (pin "1") (pinfunction "1_1") (pintype "passive"))
      (node (ref "R290") (pin "1") (pinfunction "1_1") (pintype "passive"))
      (node (ref "R294") (pin "2") (pinfunction "2_2") (pintype "passive"))
      (node (ref "R296") (pin "2") (pinfunction "2_2") (pintype "passive"))
      (node (ref "R298") (pin "2") (pinfunction "2_2") (pintype "passive"))
      (node (ref "R303") (pin "2") (pinfunction "2_2") (pintype "passive"))
      (node (ref "R304") (pin "1") (pinfunction "1_1") (pintype "passive"))
      (node (ref "R306") (pin "1") (pinfunction "1_1") (pintype "passive"))
      (node (ref "R307") (pin "2") (pinfunction "2_2") (pintype "passive"))
      (node (ref "R310") (pin "1") (pinfunction "1_1") (pintype "passive"))
      (node (ref "SW1") (pin "1") (pinfunction "1_1") (pintype "passive"))
      (node (ref "XT1") (pin "2") (pinfunction "GND_2") (pintype "passive"))
      (node (ref "XT1") (pin "4") (pinfunction "GND_4") (pintype "passive"))
    )
    (net (code "73") (name "Net-(C706-Pad1)") (class "Default")
      (node (ref "C706") (pin "1") (pinfunction "1_1") (pintype "passive"))
      (node (ref "FR88") (pin "2") (pinfunction "2_2") (pintype "passive"))
      (node (ref "J27") (pin "11") (pinfunction "Shield_11") (pintype "passive"))
      (node (ref "J27") (pin "12") (pinfunction "Shield_12") (pintype "passive"))
    )
    (net (code "74") (name "Net-(IC42A-AVDD)") (class "Default")
      (node (ref "C714") (pin "1") (pinfunction "1_1") (pintype "passive"))
      (node (ref "C715") (pin "2") (pinfunction "2_2") (pintype "passive"))
      (node (ref "FR92") (pin "1") (pinfunction "1_1") (pintype "passive"))
      (node (ref "IC42") (pin "A7") (pinfunction "AVDD_A7") (pintype "power_in"))
    )
    (net (code "75") (name "Net-(IC42A-U3RXVDDQ)") (class "Default")
      (node (ref "C716") (pin "1") (pinfunction "1_1") (pintype "passive"))
      (node (ref "C717") (pin "2") (pinfunction "2_2") (pintype "passive"))
      (node (ref "FR93") (pin "1") (pinfunction "1_1") (pintype "passive"))
      (node (ref "IC42") (pin "A2") (pinfunction "U3RXVDDQ_A2") (pintype "power_in"))
    )
    (net (code "76") (name "Net-(IC42A-U3TXVDDQ)") (class "Default")
      (node (ref "C718") (pin "1") (pinfunction "1_1") (pintype "passive"))
      (node (ref "C719") (pin "2") (pinfunction "2_2") (pintype "passive"))
      (node (ref "FR94") (pin "1") (pinfunction "1_1") (pintype "passive"))
      (node (ref "IC42") (pin "B5") (pinfunction "U3TXVDDQ_B5") (pintype "power_in"))
    )
    (net (code "77") (name "Net-(IC42B-FSLC[0])") (class "Default")
      (node (ref "IC42") (pin "B2") (pinfunction "FSLC[0]_B2") (pintype "passive"))
      (node (ref "R294") (pin "1") (pinfunction "1_1") (pintype "passive"))
    )
    (net (code "78") (name "Net-(IC42B-FSLC[1])") (class "Default")
      (node (ref "IC42") (pin "B4") (pinfunction "FSLC[1]_B4") (pintype "passive"))
      (node (ref "R296") (pin "1") (pinfunction "1_1") (pintype "passive"))
    )
    (net (code "79") (name "Net-(IC42B-FSLC[2])") (class "Default")
      (node (ref "IC42") (pin "E6") (pinfunction "FSLC[2]_E6") (pintype "passive"))
      (node (ref "R298") (pin "1") (pinfunction "1_1") (pintype "passive"))
    )
    (net (code "80") (name "Net-(IC42B-R_USB2)") (class "Default")
      (node (ref "IC42") (pin "C8") (pinfunction "R_USB2_C8") (pintype "passive"))
      (node (ref "R304") (pin "2") (pinfunction "2_2") (pintype "passive"))
    )
    (net (code "81") (name "Net-(IC42B-R_USB3)") (class "Default")
      (node (ref "IC42") (pin "B3") (pinfunction "R_USB3_B3") (pintype "passive"))
      (node (ref "R306") (pin "2") (pinfunction "2_2") (pintype "passive"))
    )
    (net (code "82") (name "Net-(IC42C-GPIO[0])") (class "Default")
      (node (ref "IC42") (pin "F10") (pinfunction "GPIO[0]_F10") (pintype "passive"))
      (node (ref "R284") (pin "1") (pinfunction "1_1") (pintype "passive"))
    )
    (net (code "83") (name "Net-(IC42C-GPIO[1])") (class "Default")
      (node (ref "IC42") (pin "F9") (pinfunction "GPIO[1]_F9") (pintype "passive"))
      (node (ref "R284") (pin "3") (pinfunction "3_3") (pintype "passive"))
    )
    (net (code "84") (name "Net-(IC42C-GPIO[2])") (class "Default")
      (node (ref "IC42") (pin "F7") (pinfunction "GPIO[2]_F7") (pintype "passive"))
      (node (ref "R284") (pin "5") (pinfunction "5_5") (pintype "passive"))
    )
    (net (code "85") (name "Net-(IC42C-GPIO[3])") (class "Default")
      (node (ref "IC42") (pin "G10") (pinfunction "GPIO[3]_G10") (pintype "passive"))
      (node (ref "R284") (pin "7") (pinfunction "7_7") (pintype "passive"))
    )
    (net (code "86") (name "Net-(IC42C-GPIO[4])") (class "Default")
      (node (ref "IC42") (pin "G9") (pinfunction "GPIO[4]_G9") (pintype "passive"))
      (node (ref "R285") (pin "1") (pinfunction "1_1") (pintype "passive"))
    )
    (net (code "87") (name "Net-(IC42C-GPIO[5])") (class "Default")
      (node (ref "IC42") (pin "F8") (pinfunction "GPIO[5]_F8") (pintype "passive"))
      (node (ref "R285") (pin "3") (pinfunction "3_3") (pintype "passive"))
    )
    (net (code "88") (name "Net-(IC42C-GPIO[6])") (class "Default")
      (node (ref "IC42") (pin "H10") (pinfunction "GPIO[6]_H10") (pintype "passive"))
      (node (ref "R285") (pin "5") (pinfunction "5_5") (pintype "passive"))
    )
    (net (code "89") (name "Net-(IC42C-GPIO[7])") (class "Default")
      (node (ref "IC42") (pin "H9") (pinfunction "GPIO[7]_H9") (pintype "passive"))
      (node (ref "R285") (pin "7") (pinfunction "7_7") (pintype "passive"))
    )
    (net (code "90") (name "Net-(IC42C-GPIO[8])") (class "Default")
      (node (ref "IC42") (pin "J10") (pinfunction "GPIO[8]_J10") (pintype "passive"))
      (node (ref "R289") (pin "1") (pinfunction "1_1") (pintype "passive"))
    )
    (net (code "91") (name "Net-(IC42C-GPIO[9])") (class "Default")
      (node (ref "IC42") (pin "J9") (pinfunction "GPIO[9]_J9") (pintype "passive"))
      (node (ref "R289") (pin "3") (pinfunction "3_3") (pintype "passive"))
    )
    (net (code "92") (name "Net-(IC42C-GPIO[10])") (class "Default")
      (node (ref "IC42") (pin "K11") (pinfunction "GPIO[10]_K11") (pintype "passive"))
      (node (ref "R289") (pin "5") (pinfunction "5_5") (pintype "passive"))
    )
    (net (code "93") (name "Net-(IC42C-GPIO[11])") (class "Default")
      (node (ref "IC42") (pin "L10") (pinfunction "GPIO[11]_L10") (pintype "passive"))
      (node (ref "R289") (pin "7") (pinfunction "7_7") (pintype "passive"))
    )
    (net (code "94") (name "Net-(IC42C-GPIO[12])") (class "Default")
      (node (ref "IC42") (pin "K10") (pinfunction "GPIO[12]_K10") (pintype "passive"))
      (node (ref "R291") (pin "1") (pinfunction "1_1") (pintype "passive"))
    )
    (net (code "95") (name "Net-(IC42C-GPIO[13])") (class "Default")
      (node (ref "IC42") (pin "K9") (pinfunction "GPIO[13]_K9") (pintype "passive"))
      (node (ref "R291") (pin "3") (pinfunction "3_3") (pintype "passive"))
    )
    (net (code "96") (name "Net-(IC42C-GPIO[14])") (class "Default")
      (node (ref "IC42") (pin "J8") (pinfunction "GPIO[14]_J8") (pintype "passive"))
      (node (ref "R291") (pin "5") (pinfunction "5_5") (pintype "passive"))
    )
    (net (code "97") (name "Net-(IC42C-GPIO[15])") (class "Default")
      (node (ref "IC42") (pin "G8") (pinfunction "GPIO[15]_G8") (pintype "passive"))
      (node (ref "R291") (pin "7") (pinfunction "7_7") (pintype "passive"))
    )
    (net (code "98") (name "Net-(IC42C-GPIO[17])") (class "Default")
      (node (ref "IC42") (pin "K8") (pinfunction "GPIO[17]_K8") (pintype "passive"))
      (node (ref "R293") (pin "1") (pinfunction "1_1") (pintype "passive"))
    )
    (net (code "99") (name "Net-(IC42C-GPIO[18])") (class "Default")
      (node (ref "IC42") (pin "K7") (pinfunction "GPIO[18]_K7") (pintype "passive"))
      (node (ref "R295") (pin "1") (pinfunction "1_1") (pintype "passive"))
    )
    (net (code "100") (name "Net-(IC42C-GPIO[19])") (class "Default")
      (node (ref "IC42") (pin "J7") (pinfunction "GPIO[19]_J7") (pintype "passive"))
      (node (ref "R295") (pin "3") (pinfunction "3_3") (pintype "passive"))
    )
    (net (code "101") (name "Net-(IC42C-GPIO[20])") (class "Default")
      (node (ref "IC42") (pin "H7") (pinfunction "GPIO[20]_H7") (pintype "passive"))
      (node (ref "R295") (pin "5") (pinfunction "5_5") (pintype "passive"))
    )
    (net (code "102") (name "Net-(IC42C-GPIO[21])") (class "Default")
      (node (ref "IC42") (pin "G7") (pinfunction "GPIO[21]_G7") (pintype "passive"))
      (node (ref "R295") (pin "7") (pinfunction "7_7") (pintype "passive"))
    )
    (net (code "103") (name "Net-(IC42C-GPIO[22])") (class "Default")
      (node (ref "IC42") (pin "G6") (pinfunction "GPIO[22]_G6") (pintype "passive"))
      (node (ref "R301") (pin "1") (pinfunction "1_1") (pintype "passive"))
    )
    (net (code "104") (name "Net-(IC42C-GPIO[23])") (class "Default")
      (node (ref "IC42") (pin "K6") (pinfunction "GPIO[23]_K6") (pintype "passive"))
      (node (ref "R301") (pin "3") (pinfunction "3_3") (pintype "passive"))
    )
    (net (code "105") (name "Net-(IC42C-GPIO[24])") (class "Default")
      (node (ref "IC42") (pin "H8") (pinfunction "GPIO[24]_H8") (pintype "passive"))
      (node (ref "R301") (pin "5") (pinfunction "5_5") (pintype "passive"))
    )
    (net (code "106") (name "Net-(IC42C-GPIO[25])") (class "Default")
      (node (ref "IC42") (pin "G5") (pinfunction "GPIO[25]_G5") (pintype "passive"))
      (node (ref "R301") (pin "7") (pinfunction "7_7") (pintype "passive"))
    )
    (net (code "107") (name "Net-(IC42C-GPIO[26])") (class "Default")
      (node (ref "IC42") (pin "H6") (pinfunction "GPIO[26]_H6") (pintype "passive"))
      (node (ref "R308") (pin "1") (pinfunction "1_1") (pintype "passive"))
    )
    (net (code "108") (name "Net-(IC42C-GPIO[27])") (class "Default")
      (node (ref "IC42") (pin "K5") (pinfunction "GPIO[27]_K5") (pintype "passive"))
      (node (ref "R308") (pin "3") (pinfunction "3_3") (pintype "passive"))
    )
    (net (code "109") (name "Net-(IC42C-GPIO[28])") (class "Default")
      (node (ref "IC42") (pin "J5") (pinfunction "GPIO[28]_J5") (pintype "passive"))
      (node (ref "R308") (pin "5") (pinfunction "5_5") (pintype "passive"))
    )
    (net (code "110") (name "Net-(IC42C-GPIO[29])") (class "Default")
      (node (ref "IC42") (pin "H5") (pinfunction "GPIO[29]_H5") (pintype "passive"))
      (node (ref "R308") (pin "7") (pinfunction "7_7") (pintype "passive"))
    )
    (net (code "111") (name "Net-(IC42C-INT#)") (class "Default")
      (node (ref "IC42") (pin "L8") (pinfunction "INT#_L8") (pintype "passive"))
      (node (ref "R309") (pin "1") (pinfunction "1_1") (pintype "passive"))
    )
    (net (code "112") (name "Net-(IC42C-PCLK)") (class "Default")
      (node (ref "IC42") (pin "J6") (pinfunction "PCLK_J6") (pintype "input"))
      (node (ref "R292") (pin "1") (pinfunction "1_1") (pintype "passive"))
    )
    (net (code "113") (name "Net-(IC42C-PMODE[0])") (class "Default")
      (node (ref "IC42") (pin "G4") (pinfunction "PMODE[0]_G4") (pintype "passive"))
      (node (ref "R302") (pin "1") (pinfunction "1_1") (pintype "passive"))
    )
    (net (code "114") (name "Net-(IC42C-PMODE[1])") (class "Default")
      (node (ref "IC42") (pin "H4") (pinfunction "PMODE[1]_H4") (pintype "passive"))
      (node (ref "R305") (pin "1") (pinfunction "1_1") (pintype "passive"))
    )
    (net (code "115") (name "Net-(IC42C-PMODE[2])") (class "Default")
      (node (ref "IC42") (pin "L4") (pinfunction "PMODE[2]_L4") (pintype "passive"))
      (node (ref "R307") (pin "1") (pinfunction "1_1") (pintype "passive"))
    )
    (net (code "116") (name "Net-(IC43-HOLD)") (class "Default")
      (node (ref "IC43") (pin "7") (pinfunction "HOLD_7") (pintype "passive"))
      (node (ref "R314") (pin "1") (pinfunction "1_1") (pintype "passive"))
    )
    (net (code "117") (name "Net-(IC43-S)") (class "Default")
      (node (ref "IC43") (pin "1") (pinfunction "S_1") (pintype "passive"))
      (node (ref "J28") (pin "2") (pinfunction "2_2") (pintype "passive"))
      (node (ref "R312") (pin "1") (pinfunction "1_1") (pintype "passive"))
      (node (ref "R313") (pin "2") (pinfunction "2_2") (pintype "passive"))
    )
    (net (code "118") (name "Net-(IC43-W)") (class "Default")
      (node (ref "IC43") (pin "3") (pinfunction "W_3") (pintype "passive"))
      (node (ref "R315") (pin "1") (pinfunction "1_1") (pintype "passive"))
    )
    (net (code "119") (name "Net-(J27-GND_DRAIN)") (class "Default")
      (node (ref "J27") (pin "8") (pinfunction "GND_DRAIN_8") (pintype "passive"))
      (node (ref "R290") (pin "2") (pinfunction "2_2") (pintype "passive"))
    )
    (net (code "120") (name "Net-(J27-VBUS)") (class "Default")
      (node (ref "FR87") (pin "1") (pinfunction "1_1") (pintype "passive"))
      (node (ref "J27") (pin "1") (pinfunction "VBUS_1") (pintype "passive"))
    )
    (net (code "121") (name "Net-(J29-Pad10)") (class "Default")
      (node (ref "J29") (pin "10") (pinfunction "10_10") (pintype "passive"))
      (node (ref "R316") (pin "2") (pinfunction "2_2") (pintype "passive"))
      (node (ref "R317") (pin "2") (pinfunction "2_2") (pintype "passive"))
    )
    (net (code "122") (name "VCC1P2") (class "Default")
      (node (ref "FR89") (pin "1") (pinfunction "1_1") (pintype "passive"))
      (node (ref "FR92") (pin "2") (pinfunction "2_2") (pintype "passive"))
      (node (ref "FR93") (pin "2") (pinfunction "2_2") (pintype "passive"))
      (node (ref "FR94") (pin "2") (pinfunction "2_2") (pintype "passive"))
    )
    (net (code "123") (name "VCC1P2_FX3") (class "Default")
      (node (ref "C707") (pin "2") (pinfunction "2_2") (pintype "passive"))
      (node (ref "C731") (pin "1") (pinfunction "1_1") (pintype "passive"))
      (node (ref "C732") (pin "1") (pinfunction "1_1") (pintype "passive"))
      (node (ref "C733") (pin "1") (pinfunction "1_1") (pintype "passive"))
      (node (ref "C734") (pin "1") (pinfunction "1_1") (pintype "passive"))
      (node (ref "C735") (pin "1") (pinfunction "1_1") (pintype "passive"))
      (node (ref "C736") (pin "1") (pinfunction "1_1") (pintype "passive"))
      (node (ref "C737") (pin "1") (pinfunction "1_1") (pintype "passive"))
      (node (ref "C738") (pin "1") (pinfunction "1_1") (pintype "passive"))
      (node (ref "C739") (pin "2") (pinfunction "2_2") (pintype "passive"))
      (node (ref "C740") (pin "2") (pinfunction "2_2") (pintype "passive"))
      (node (ref "C741") (pin "2") (pinfunction "2_2") (pintype "passive"))
      (node (ref "C742") (pin "2") (pinfunction "2_2") (pintype "passive"))
      (node (ref "C743") (pin "2") (pinfunction "2_2") (pintype "passive"))
      (node (ref "C744") (pin "2") (pinfunction "2_2") (pintype "passive"))
      (node (ref "C745") (pin "2") (pinfunction "2_2") (pintype "passive"))
      (node (ref "C746") (pin "2") (pinfunction "2_2") (pintype "passive"))
      (node (ref "FR89") (pin "2") (pinfunction "2_2") (pintype "passive"))
      (node (ref "IC42") (pin "B10") (pinfunction "VDD_B10") (pintype "power_in"))
      (node (ref "IC42") (pin "C3") (pinfunction "VDD_C3") (pintype "power_in"))
      (node (ref "IC42") (pin "E9") (pinfunction "VDD_E9") (pintype "power_in"))
      (node (ref "IC42") (pin "F11") (pinfunction "VDD_F11") (pintype "power_in"))
      (node (ref "IC42") (pin "H1") (pinfunction "VDD_H1") (pintype "power_in"))
      (node (ref "IC42") (pin "J11") (pinfunction "VDD_J11") (pintype "power_in"))
      (node (ref "IC42") (pin "L5") (pinfunction "VDD_L5") (pintype "power_in"))
      (node (ref "IC42") (pin "L7") (pinfunction "VDD_L7") (pintype "power_in"))
    )
    (net (code "124") (name "VCC1P8") (class "Default")
      (node (ref "FR95") (pin "1") (pinfunction "1_1") (pintype "passive"))
    )
    (net (code "125") (name "VCC1P8_FX3") (class "Default")
      (node (ref "C713") (pin "2") (pinfunction "2_2") (pintype "passive"))
      (node (ref "C727") (pin "1") (pinfunction "1_1") (pintype "passive"))
      (node (ref "C728") (pin "1") (pinfunction "1_1") (pintype "passive"))
      (node (ref "C729") (pin "2") (pinfunction "2_2") (pintype "passive"))
      (node (ref "C730") (pin "2") (pinfunction "2_2") (pintype "passive"))
      (node (ref "FR95") (pin "2") (pinfunction "2_2") (pintype "passive"))
      (node (ref "IC42") (pin "E3") (pinfunction "VIO3_E3") (pintype "power_in"))
      (node (ref "IC42") (pin "H11") (pinfunction "VIO1_1_H11") (pintype "power_in"))
      (node (ref "IC42") (pin "L9") (pinfunction "VIO1_2_L9") (pintype "power_in"))
      (node (ref "R297") (pin "1") (pinfunction "1_1") (pintype "passive"))
      (node (ref "R299") (pin "1") (pinfunction "1_1") (pintype "passive"))
      (node (ref "R300") (pin "1") (pinfunction "1_1") (pintype "passive"))
      (node (ref "R302") (pin "2") (pinfunction "2_2") (pintype "passive"))
      (node (ref "R305") (pin "2") (pinfunction "2_2") (pintype "passive"))
      (node (ref "R309") (pin "2") (pinfunction "2_2") (pintype "passive"))
    )
    (net (code "126") (name "VCC3P3") (class "Default")
      (node (ref "C711") (pin "1") (pinfunction "1_1") (pintype "passive"))
      (node (ref "FR90") (pin "2") (pinfunction "2_2") (pintype "passive"))
      (node (ref "FR96") (pin "1") (pinfunction "1_1") (pintype "passive"))
      (node (ref "IC43") (pin "8") (pinfunction "VCC_8") (pintype "passive"))
      (node (ref "J29") (pin "1") (pinfunction "1_1") (pintype "passive"))
      (node (ref "R312") (pin "2") (pinfunction "2_2") (pintype "passive"))
      (node (ref "R314") (pin "2") (pinfunction "2_2") (pintype "passive"))
      (node (ref "R315") (pin "2") (pinfunction "2_2") (pintype "passive"))
    )
    (net (code "127") (name "VCC3P3_CLK") (class "Default")
      (node (ref "FR91") (pin "2") (pinfunction "2_2") (pintype "passive"))
    )
    (net (code "128") (name "VCC3P3_FX3") (class "Default")
      (node (ref "C720") (pin "1") (pinfunction "1_1") (pintype "passive"))
      (node (ref "C721") (pin "2") (pinfunction "2_2") (pintype "passive"))
      (node (ref "C722") (pin "2") (pinfunction "2_2") (pintype "passive"))
      (node (ref "C723") (pin "1") (pinfunction "1_1") (pintype "passive"))
      (node (ref "C724") (pin "2") (pinfunction "2_2") (pintype "passive"))
      (node (ref "C725") (pin "1") (pinfunction "1_1") (pintype "passive"))
      (node (ref "C726") (pin "2") (pinfunction "2_2") (pintype "passive"))
      (node (ref "FR96") (pin "2") (pinfunction "2_2") (pintype "passive"))
      (node (ref "IC42") (pin "B1") (pinfunction "VIO4_B1") (pintype "power_in"))
      (node (ref "IC42") (pin "C11") (pinfunction "VIO5_C11") (pintype "power_in"))
      (node (ref "IC42") (pin "E10") (pinfunction "VBATT_E10") (pintype "power_in"))
      (node (ref "IC42") (pin "F1") (pinfunction "VIO2_F1") (pintype "power_in"))
    )
    (net (code "129") (name "VCC_CFX3") (class "Default")
      (node (ref "C708") (pin "1") (pinfunction "1_1") (pintype "passive"))
      (node (ref "C709") (pin "2") (pinfunction "2_2") (pintype "passive"))
      (node (ref "C710") (pin "2") (pinfunction "2_2") (pintype "passive"))
      (node (ref "FR90") (pin "1") (pinfunction "1_1") (pintype "passive"))
      (node (ref "FR91") (pin "1") (pinfunction "1_1") (pintype "passive"))
      (node (ref "IC42") (pin "B6") (pinfunction "CVDDQ_B6") (pintype "power_in"))
      (node (ref "R311") (pin "1") (pinfunction "1_1") (pintype "passive"))
    )
    (net (code "130") (name "unconnected-(FL6-Pad1)") (class "Default")
      (node (ref "FL6") (pin "1") (pintype "passive+no_connect"))
    )
    (net (code "131") (name "unconnected-(IC42B-CLKIN-PadD7)") (class "Default")
      (node (ref "IC42") (pin "D7") (pinfunction "CLKIN_D7") (pintype "input+no_connect"))
    )
    (net (code "132") (name "unconnected-(IC42B-CLKIN_32-PadD6)") (class "Default")
      (node (ref "IC42") (pin "D6") (pinfunction "CLKIN_32_D6") (pintype "input+no_connect"))
    )
    (net (code "133") (name "unconnected-(IC42B-GPIO[57]-PadC4)") (class "Default")
      (node (ref "IC42") (pin "C4") (pinfunction "GPIO[57]_C4") (pintype "passive+no_connect"))
    )
    (net (code "134") (name "unconnected-(IC42B-NC-PadA11)") (class "Default")
      (node (ref "IC42") (pin "A11") (pinfunction "NC_A11") (pintype "passive+no_connect"))
    )
    (net (code "135") (name "unconnected-(IC42B-O[60]-PadD11)") (class "Default")
      (node (ref "IC42") (pin "D11") (pinfunction "O[60]_D11") (pintype "passive+no_connect"))
    )
    (net (code "136") (name "unconnected-(IC42C-GPIO[33]-PadK2)") (class "Default")
      (node (ref "IC42") (pin "K2") (pinfunction "GPIO[33]_K2") (pintype "passive+no_connect"))
    )
    (net (code "137") (name "unconnected-(IC42C-GPIO[34]-PadJ4)") (class "Default")
      (node (ref "IC42") (pin "J4") (pinfunction "GPIO[34]_J4") (pintype "passive+no_connect"))
    )
    (net (code "138") (name "unconnected-(IC42C-GPIO[35]-PadK1)") (class "Default")
      (node (ref "IC42") (pin "K1") (pinfunction "GPIO[35]_K1") (pintype "passive+no_connect"))
    )
    (net (code "139") (name "unconnected-(IC42C-GPIO[36]-PadJ2)") (class "Default")
      (node (ref "IC42") (pin "J2") (pinfunction "GPIO[36]_J2") (pintype "passive+no_connect"))
    )
    (net (code "140") (name "unconnected-(IC42C-GPIO[37]-PadJ3)") (class "Default")
      (node (ref "IC42") (pin "J3") (pinfunction "GPIO[37]_J3") (pintype "passive+no_connect"))
    )
    (net (code "141") (name "unconnected-(IC42C-GPIO[38]-PadJ1)") (class "Default")
      (node (ref "IC42") (pin "J1") (pinfunction "GPIO[38]_J1") (pintype "passive+no_connect"))
    )
    (net (code "142") (name "unconnected-(IC42C-GPIO[39]-PadH2)") (class "Default")
      (node (ref "IC42") (pin "H2") (pinfunction "GPIO[39]_H2") (pintype "passive+no_connect"))
    )
    (net (code "143") (name "unconnected-(IC42C-GPIO[40]-PadH3)") (class "Default")
      (node (ref "IC42") (pin "H3") (pinfunction "GPIO[40]_H3") (pintype "passive+no_connect"))
    )
    (net (code "144") (name "unconnected-(J29-Pad7)") (class "Default")
      (node (ref "J29") (pin "7") (pinfunction "7_7") (pintype "passive+no_connect"))
    )
    (net (code "145") (name "unconnected-(J29-Pad9)") (class "Default")
      (node (ref "J29") (pin "9") (pinfunction "9_9") (pintype "passive+no_connect"))
    )
  )
)
